# display_adapter.net
KiCad netlist of a schematic drawn in EAGLE
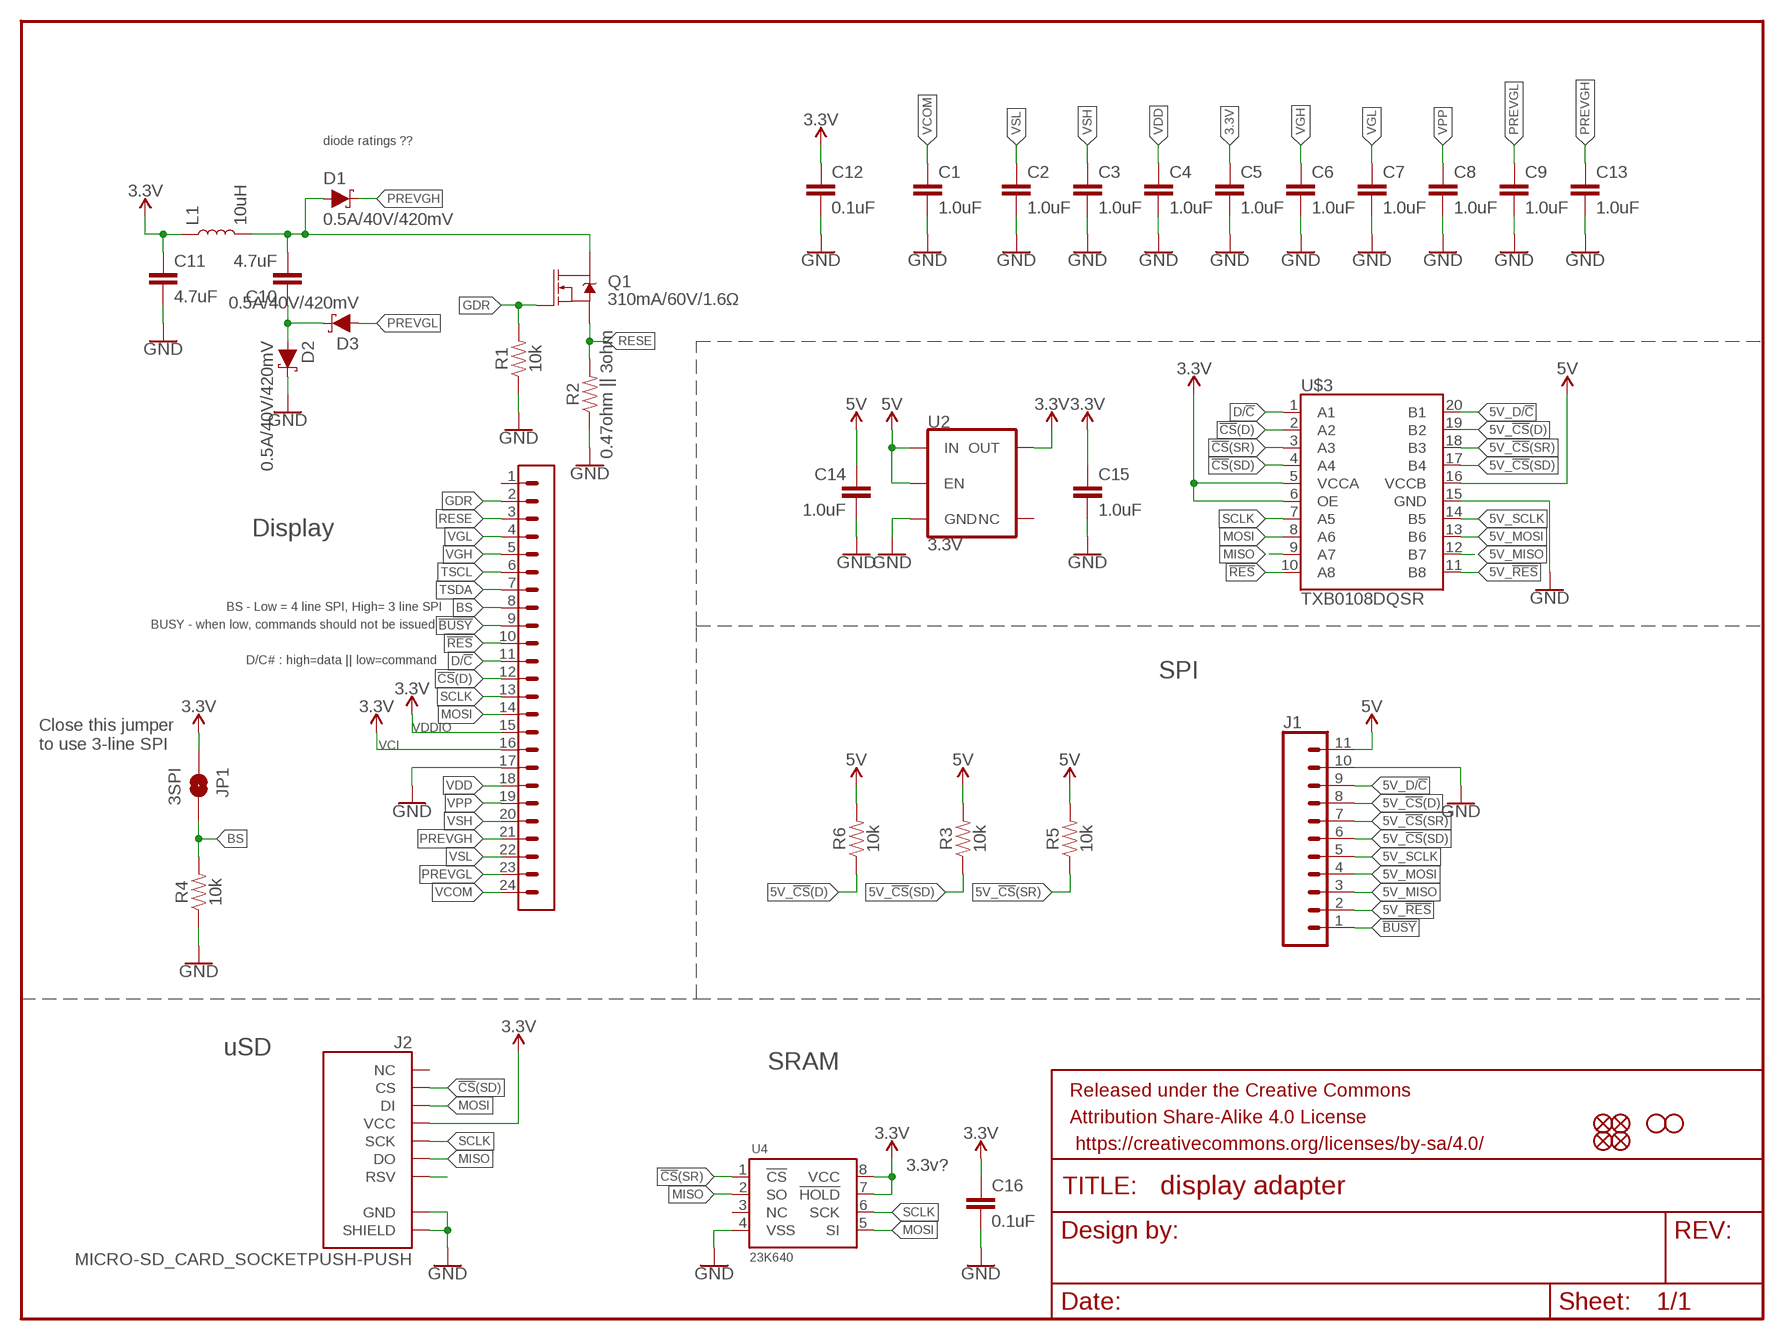
[diagram p0: schematic, sheet 1]

(export (version "E")
  (design (tool "Eeschema 10.0.6"))
  (components
    (comp (ref "C1")
      (value "1.0uF")
      (footprint "eagle-import:0603")
      (libsource (lib "eagle-import") (part "1.0UF-0603-16V-10%"))
    )
    (comp (ref "C2")
      (value "1.0uF")
      (footprint "eagle-import:0805")
      (libsource (lib "eagle-import") (part "1.0UF-0805-25V-10%"))
    )
    (comp (ref "C3")
      (value "1.0uF")
      (footprint "eagle-import:0805")
      (libsource (lib "eagle-import") (part "1.0UF-0805-25V-10%"))
    )
    (comp (ref "C4")
      (value "1.0uF")
      (footprint "eagle-import:0805")
      (libsource (lib "eagle-import") (part "1.0UF-0805-25V-10%"))
    )
    (comp (ref "C5")
      (value "1.0uF")
      (footprint "eagle-import:0805")
      (libsource (lib "eagle-import") (part "1.0UF-0805-25V-10%"))
    )
    (comp (ref "C6")
      (value "1.0uF")
      (footprint "eagle-import:0805")
      (libsource (lib "eagle-import") (part "1.0UF-0805-25V-10%"))
    )
    (comp (ref "C7")
      (value "1.0uF")
      (footprint "eagle-import:0805")
      (libsource (lib "eagle-import") (part "1.0UF-0805-25V-10%"))
    )
    (comp (ref "C8")
      (value "1.0uF")
      (footprint "eagle-import:0805")
      (libsource (lib "eagle-import") (part "1.0UF-0805-25V-10%"))
    )
    (comp (ref "C9")
      (value "1.0uF")
      (footprint "eagle-import:0805")
      (libsource (lib "eagle-import") (part "1.0UF-0805-25V-10%"))
    )
    (comp (ref "C10")
      (value "4.7uF")
      (footprint "eagle-import:0805")
      (libsource (lib "eagle-import") (part "22UF-0805-6.3V-20%"))
    )
    (comp (ref "C11")
      (value "4.7uF")
      (footprint "eagle-import:0805")
      (libsource (lib "eagle-import") (part "22UF-0805-6.3V-20%"))
    )
    (comp (ref "C12")
      (value "0.1uF")
      (footprint "eagle-import:0603")
      (libsource (lib "eagle-import") (part "0.1UF-0603-25V-(+80/-20%)"))
    )
    (comp (ref "C13")
      (value "1.0uF")
      (footprint "eagle-import:0805")
      (libsource (lib "eagle-import") (part "1.0UF-0805-25V-10%"))
    )
    (comp (ref "C14")
      (value "1.0uF")
      (footprint "eagle-import:0603")
      (libsource (lib "eagle-import") (part "1.0UF-0603-16V-10%"))
    )
    (comp (ref "C15")
      (value "1.0uF")
      (footprint "eagle-import:0603")
      (libsource (lib "eagle-import") (part "1.0UF-0603-16V-10%"))
    )
    (comp (ref "C16")
      (value "0.1uF")
      (footprint "eagle-import:0603")
      (libsource (lib "eagle-import") (part "0.1UF-0603-25V-(+80/-20%)"))
    )
    (comp (ref "D1")
      (value "0.5A/40V/420mV")
      (footprint "eagle-import:SOD-323")
      (libsource (lib "eagle-import") (part "DIODE-SCHOTTKY-PMEG4005EJ"))
    )
    (comp (ref "D2")
      (value "0.5A/40V/420mV")
      (footprint "eagle-import:SOD-323")
      (libsource (lib "eagle-import") (part "DIODE-SCHOTTKY-PMEG4005EJ"))
    )
    (comp (ref "D3")
      (value "0.5A/40V/420mV")
      (footprint "eagle-import:SOD-323")
      (libsource (lib "eagle-import") (part "DIODE-SCHOTTKY-PMEG4005EJ"))
    )
    (comp (ref "FD1")
      (value "FIDUCIALUFIDUCIAL")
      (footprint "eagle-import:FIDUCIAL-MICRO")
      (libsource (lib "eagle-import") (part "FIDUCIALUFIDUCIAL"))
    )
    (comp (ref "FD2")
      (value "FIDUCIALUFIDUCIAL")
      (footprint "eagle-import:FIDUCIAL-MICRO")
      (libsource (lib "eagle-import") (part "FIDUCIALUFIDUCIAL"))
    )
    (comp (ref "FD3")
      (value "FIDUCIALUFIDUCIAL")
      (footprint "eagle-import:FIDUCIAL-MICRO")
      (libsource (lib "eagle-import") (part "FIDUCIALUFIDUCIAL"))
    )
    (comp (ref "FD4")
      (value "FIDUCIALUFIDUCIAL")
      (footprint "eagle-import:FIDUCIAL-MICRO")
      (libsource (lib "eagle-import") (part "FIDUCIALUFIDUCIAL"))
    )
    (comp (ref "FRAME1")
      (value "FRAME-LETTER")
      (footprint "eagle-import:CREATIVE_COMMONS")
      (libsource (lib "eagle-import") (part "FRAME-LETTER"))
    )
    (comp (ref "H1")
      (value "STAND-OFF")
      (footprint "eagle-import:STAND-OFF")
      (libsource (lib "eagle-import") (part "STAND-OFF"))
    )
    (comp (ref "H2")
      (value "STAND-OFF")
      (footprint "eagle-import:STAND-OFF")
      (libsource (lib "eagle-import") (part "STAND-OFF"))
    )
    (comp (ref "J1")
      (value "CONN_111X11_NO_SILK")
      (footprint "eagle-import:1X11_NO_SILK")
      (libsource (lib "eagle-import") (part "CONN_111X11_NO_SILK"))
    )
    (comp (ref "J2")
      (value "MICRO-SD_CARD_SOCKETPUSH-PUSH")
      (footprint "eagle-import:MICRO-SD-SOCKET")
      (libsource (lib "eagle-import") (part "MICRO-SD_CARD_SOCKETPUSH-PUSH"))
    )
    (comp (ref "JP1")
      (value "3SPI")
      (footprint "eagle-import:SMT-JUMPER_2_NO_SILK")
      (libsource (lib "eagle-import") (part "JUMPER-SMT_2_NO_SILK"))
    )
    (comp (ref "L1")
      (value "10uH")
      (footprint "eagle-import:INDUCTOR_4.7UH")
      (libsource (lib "eagle-import") (part "INDUCTOR-CDRH-10UH"))
    )
    (comp (ref "Q1")
      (value "310mA/60V/1.6Ω")
      (footprint "eagle-import:SOT323")
      (libsource (lib "eagle-import") (part "MOSFET-NCH-2N7002PW"))
    )
    (comp (ref "R1")
      (value "10k")
      (footprint "eagle-import:0603")
      (libsource (lib "eagle-import") (part "10KOHM-0603-1/10W-1%"))
    )
    (comp (ref "R2")
      (value "0.47ohm || 3ohm")
      (footprint "eagle-import:0603")
      (libsource (lib "eagle-import") (part "RESISTOR0603"))
    )
    (comp (ref "R3")
      (value "10k")
      (footprint "eagle-import:0603")
      (libsource (lib "eagle-import") (part "10KOHM-0603-1/10W-1%"))
    )
    (comp (ref "R4")
      (value "10k")
      (footprint "eagle-import:0603")
      (libsource (lib "eagle-import") (part "10KOHM-0603-1/10W-1%"))
    )
    (comp (ref "R5")
      (value "10k")
      (footprint "eagle-import:0603")
      (libsource (lib "eagle-import") (part "10KOHM-0603-1/10W-1%"))
    )
    (comp (ref "R6")
      (value "10k")
      (footprint "eagle-import:0603")
      (libsource (lib "eagle-import") (part "10KOHM-0603-1/10W-1%"))
    )
    (comp (ref "U$1")
      (value "24_PIN_FPC_0.5MM")
      (footprint "eagle-import:24_PIN_FPC_0.5MM")
      (libsource (lib "eagle-import") (part "24_PIN_FPC_0.5MM"))
    )
    (comp (ref "U$3")
      (value "TXB0108DQSR")
      (footprint "eagle-import:UFDFN-20")
      (libsource (lib "eagle-import") (part "TXB0108"))
    )
    (comp (ref "U2")
      (value "3.3V")
      (footprint "eagle-import:SOT23-5")
      (libsource (lib "eagle-import") (part "V_REG_AP2112K-3.3V"))
    )
    (comp (ref "U4")
      (value "23K640")
      (footprint "eagle-import:SO08")
      (libsource (lib "eagle-import") (part "23K640"))
    )
  )
  (nets
    (net (code "1") (name "/5V_D{slash}~{C}") (class "Default")
      (node (ref "J1") (pin "9") (pinfunction "9_9") (pintype "passive"))
      (node (ref "U$3") (pin "20") (pinfunction "B1_20") (pintype "bidirectional"))
    )
    (net (code "2") (name "/5V_~{CS}(D)") (class "Default")
      (node (ref "J1") (pin "8") (pinfunction "8_8") (pintype "passive"))
      (node (ref "R6") (pin "1") (pinfunction "1_1") (pintype "passive"))
      (node (ref "U$3") (pin "19") (pinfunction "B2_19") (pintype "bidirectional"))
    )
    (net (code "3") (name "/5V_~{CS}(SD)") (class "Default")
      (node (ref "J1") (pin "6") (pinfunction "6_6") (pintype "passive"))
      (node (ref "R3") (pin "1") (pinfunction "1_1") (pintype "passive"))
      (node (ref "U$3") (pin "17") (pinfunction "B4_17") (pintype "bidirectional"))
    )
    (net (code "4") (name "/5V_~{CS}(SR)") (class "Default")
      (node (ref "J1") (pin "7") (pinfunction "7_7") (pintype "passive"))
      (node (ref "R5") (pin "1") (pinfunction "1_1") (pintype "passive"))
      (node (ref "U$3") (pin "18") (pinfunction "B3_18") (pintype "bidirectional"))
    )
    (net (code "5") (name "/5V_~{RES}") (class "Default")
      (node (ref "J1") (pin "2") (pinfunction "2_2") (pintype "passive"))
      (node (ref "U$3") (pin "11") (pinfunction "B8_11") (pintype "bidirectional"))
    )
    (net (code "6") (name "/D{slash}~{C}") (class "Default")
      (node (ref "U$1") (pin "11") (pinfunction "11_11") (pintype "bidirectional"))
      (node (ref "U$3") (pin "1") (pinfunction "A1_1") (pintype "bidirectional"))
    )
    (net (code "7") (name "/~{BUSY}") (class "Default")
      (node (ref "J1") (pin "1") (pinfunction "1_1") (pintype "passive"))
      (node (ref "U$1") (pin "9") (pinfunction "9_9") (pintype "bidirectional"))
    )
    (net (code "8") (name "/~{CS}(D)") (class "Default")
      (node (ref "U$1") (pin "12") (pinfunction "12_12") (pintype "bidirectional"))
      (node (ref "U$3") (pin "2") (pinfunction "A2_2") (pintype "bidirectional"))
    )
    (net (code "9") (name "/~{CS}(SD)") (class "Default")
      (node (ref "J2") (pin "CS") (pinfunction "CS_CS") (pintype "bidirectional"))
      (node (ref "U$3") (pin "4") (pinfunction "A4_4") (pintype "bidirectional"))
    )
    (net (code "10") (name "/~{CS}(SR)") (class "Default")
      (node (ref "U$3") (pin "3") (pinfunction "A3_3") (pintype "bidirectional"))
      (node (ref "U4") (pin "1") (pinfunction "~{CS}_1") (pintype "bidirectional"))
    )
    (net (code "11") (name "/~{RES}") (class "Default")
      (node (ref "U$1") (pin "10") (pinfunction "10_10") (pintype "bidirectional"))
      (node (ref "U$3") (pin "10") (pinfunction "A8_10") (pintype "bidirectional"))
    )
    (net (code "12") (name "3.3V") (class "Default")
      (node (ref "C11") (pin "1") (pinfunction "1_1") (pintype "passive"))
      (node (ref "C12") (pin "1") (pinfunction "1_1") (pintype "passive"))
      (node (ref "C15") (pin "1") (pinfunction "1_1") (pintype "passive"))
      (node (ref "C16") (pin "1") (pinfunction "1_1") (pintype "passive"))
      (node (ref "C5") (pin "1") (pinfunction "1_1") (pintype "passive"))
      (node (ref "J2") (pin "VCC") (pinfunction "VCC_VCC") (pintype "bidirectional"))
      (node (ref "JP1") (pin "1") (pinfunction "1_1") (pintype "passive"))
      (node (ref "L1") (pin "P$1") (pinfunction "1_P$1") (pintype "passive"))
      (node (ref "U$1") (pin "15") (pinfunction "15_15") (pintype "bidirectional"))
      (node (ref "U$1") (pin "16") (pinfunction "16_16") (pintype "bidirectional"))
      (node (ref "U$3") (pin "5") (pinfunction "VCCA_5") (pintype "bidirectional"))
      (node (ref "U$3") (pin "6") (pinfunction "OE_6") (pintype "bidirectional"))
      (node (ref "U2") (pin "5") (pinfunction "OUT_5") (pintype "passive"))
      (node (ref "U4") (pin "7") (pinfunction "~{HOLD}_7") (pintype "bidirectional"))
      (node (ref "U4") (pin "8") (pinfunction "VCC_8") (pintype "bidirectional"))
    )
    (net (code "13") (name "5V") (class "Default")
      (node (ref "C14") (pin "1") (pinfunction "1_1") (pintype "passive"))
      (node (ref "J1") (pin "11") (pinfunction "11_11") (pintype "passive"))
      (node (ref "R3") (pin "2") (pinfunction "2_2") (pintype "passive"))
      (node (ref "R5") (pin "2") (pinfunction "2_2") (pintype "passive"))
      (node (ref "R6") (pin "2") (pinfunction "2_2") (pintype "passive"))
      (node (ref "U$3") (pin "16") (pinfunction "VCCB_16") (pintype "bidirectional"))
      (node (ref "U2") (pin "1") (pinfunction "IN_1") (pintype "input"))
      (node (ref "U2") (pin "3") (pinfunction "EN_3") (pintype "input"))
    )
    (net (code "14") (name "5V_MISO") (class "Default")
      (node (ref "J1") (pin "3") (pinfunction "3_3") (pintype "passive"))
      (node (ref "U$3") (pin "12") (pinfunction "B7_12") (pintype "bidirectional"))
    )
    (net (code "15") (name "5V_MOSI") (class "Default")
      (node (ref "J1") (pin "4") (pinfunction "4_4") (pintype "passive"))
      (node (ref "U$3") (pin "13") (pinfunction "B6_13") (pintype "bidirectional"))
    )
    (net (code "16") (name "5V_SCLK") (class "Default")
      (node (ref "J1") (pin "5") (pinfunction "5_5") (pintype "passive"))
      (node (ref "U$3") (pin "14") (pinfunction "B5_14") (pintype "bidirectional"))
    )
    (net (code "17") (name "BS") (class "Default")
      (node (ref "JP1") (pin "2") (pinfunction "2_2") (pintype "passive"))
      (node (ref "R4") (pin "2") (pinfunction "2_2") (pintype "passive"))
      (node (ref "U$1") (pin "8") (pinfunction "8_8") (pintype "bidirectional"))
    )
    (net (code "18") (name "GDR") (class "Default")
      (node (ref "Q1") (pin "1") (pinfunction "G_1") (pintype "bidirectional"))
      (node (ref "R1") (pin "2") (pinfunction "2_2") (pintype "passive"))
      (node (ref "U$1") (pin "2") (pinfunction "2_2") (pintype "bidirectional"))
    )
    (net (code "19") (name "GND") (class "Default")
      (node (ref "C1") (pin "2") (pinfunction "2_2") (pintype "passive"))
      (node (ref "C11") (pin "2") (pinfunction "2_2") (pintype "passive"))
      (node (ref "C12") (pin "2") (pinfunction "2_2") (pintype "passive"))
      (node (ref "C13") (pin "2") (pinfunction "2_2") (pintype "passive"))
      (node (ref "C14") (pin "2") (pinfunction "2_2") (pintype "passive"))
      (node (ref "C15") (pin "2") (pinfunction "2_2") (pintype "passive"))
      (node (ref "C16") (pin "2") (pinfunction "2_2") (pintype "passive"))
      (node (ref "C2") (pin "2") (pinfunction "2_2") (pintype "passive"))
      (node (ref "C3") (pin "2") (pinfunction "2_2") (pintype "passive"))
      (node (ref "C4") (pin "2") (pinfunction "2_2") (pintype "passive"))
      (node (ref "C5") (pin "2") (pinfunction "2_2") (pintype "passive"))
      (node (ref "C6") (pin "2") (pinfunction "2_2") (pintype "passive"))
      (node (ref "C7") (pin "2") (pinfunction "2_2") (pintype "passive"))
      (node (ref "C8") (pin "2") (pinfunction "2_2") (pintype "passive"))
      (node (ref "C9") (pin "2") (pinfunction "2_2") (pintype "passive"))
      (node (ref "D2") (pin "C") (pinfunction "C_C") (pintype "passive"))
      (node (ref "J1") (pin "10") (pinfunction "10_10") (pintype "passive"))
      (node (ref "J2") (pin "CD1") (pinfunction "SHIELD_CD1") (pintype "bidirectional"))
      (node (ref "J2") (pin "GND") (pinfunction "GND_GND") (pintype "bidirectional"))
      (node (ref "R1") (pin "1") (pinfunction "1_1") (pintype "passive"))
      (node (ref "R2") (pin "1") (pinfunction "1_1") (pintype "passive"))
      (node (ref "R4") (pin "1") (pinfunction "1_1") (pintype "passive"))
      (node (ref "U$1") (pin "17") (pinfunction "17_17") (pintype "bidirectional"))
      (node (ref "U$3") (pin "15") (pinfunction "GND_15") (pintype "bidirectional"))
      (node (ref "U2") (pin "2") (pinfunction "GND_2") (pintype "input"))
      (node (ref "U4") (pin "4") (pinfunction "VSS_4") (pintype "bidirectional"))
    )
    (net (code "20") (name "MISO") (class "Default")
      (node (ref "J2") (pin "DO") (pinfunction "DO_DO") (pintype "bidirectional"))
      (node (ref "U$3") (pin "9") (pinfunction "A7_9") (pintype "bidirectional"))
      (node (ref "U4") (pin "2") (pinfunction "SO_2") (pintype "bidirectional"))
    )
    (net (code "21") (name "MOSI") (class "Default")
      (node (ref "J2") (pin "DI") (pinfunction "DI_DI") (pintype "bidirectional"))
      (node (ref "U$1") (pin "14") (pinfunction "14_14") (pintype "bidirectional"))
      (node (ref "U$3") (pin "8") (pinfunction "A6_8") (pintype "bidirectional"))
      (node (ref "U4") (pin "5") (pinfunction "SI_5") (pintype "bidirectional"))
    )
    (net (code "22") (name "Net-(C10-Pad1)") (class "Default")
      (node (ref "C10") (pin "1") (pinfunction "1_1") (pintype "passive"))
      (node (ref "D2") (pin "A") (pinfunction "A_A") (pintype "passive"))
      (node (ref "D3") (pin "C") (pinfunction "C_C") (pintype "passive"))
    )
    (net (code "23") (name "Net-(L1-2)") (class "Default")
      (node (ref "C10") (pin "2") (pinfunction "2_2") (pintype "passive"))
      (node (ref "D1") (pin "A") (pinfunction "A_A") (pintype "passive"))
      (node (ref "L1") (pin "P$2") (pinfunction "2_P$2") (pintype "passive"))
      (node (ref "Q1") (pin "3") (pinfunction "D_3") (pintype "bidirectional"))
    )
    (net (code "24") (name "PREVGH") (class "Default")
      (node (ref "C13") (pin "1") (pinfunction "1_1") (pintype "passive"))
      (node (ref "D1") (pin "C") (pinfunction "C_C") (pintype "passive"))
      (node (ref "U$1") (pin "21") (pinfunction "21_21") (pintype "bidirectional"))
    )
    (net (code "25") (name "PREVGL") (class "Default")
      (node (ref "C9") (pin "1") (pinfunction "1_1") (pintype "passive"))
      (node (ref "D3") (pin "A") (pinfunction "A_A") (pintype "passive"))
      (node (ref "U$1") (pin "23") (pinfunction "23_23") (pintype "bidirectional"))
    )
    (net (code "26") (name "RESE") (class "Default")
      (node (ref "Q1") (pin "2") (pinfunction "S_2") (pintype "bidirectional"))
      (node (ref "R2") (pin "2") (pinfunction "2_2") (pintype "passive"))
      (node (ref "U$1") (pin "3") (pinfunction "3_3") (pintype "bidirectional"))
    )
    (net (code "27") (name "SCLK") (class "Default")
      (node (ref "J2") (pin "SCLK") (pinfunction "SCK_SCLK") (pintype "bidirectional"))
      (node (ref "U$1") (pin "13") (pinfunction "13_13") (pintype "bidirectional"))
      (node (ref "U$3") (pin "7") (pinfunction "A5_7") (pintype "bidirectional"))
      (node (ref "U4") (pin "6") (pinfunction "SCK_6") (pintype "bidirectional"))
    )
    (net (code "28") (name "TSCL") (class "Default")
      (node (ref "U$1") (pin "6") (pinfunction "6_6") (pintype "bidirectional"))
    )
    (net (code "29") (name "TSDA") (class "Default")
      (node (ref "U$1") (pin "7") (pinfunction "7_7") (pintype "bidirectional"))
    )
    (net (code "30") (name "VCOM") (class "Default")
      (node (ref "C1") (pin "1") (pinfunction "1_1") (pintype "passive"))
      (node (ref "U$1") (pin "24") (pinfunction "24_24") (pintype "bidirectional"))
    )
    (net (code "31") (name "VDD") (class "Default")
      (node (ref "C4") (pin "1") (pinfunction "1_1") (pintype "passive"))
      (node (ref "U$1") (pin "18") (pinfunction "18_18") (pintype "bidirectional"))
    )
    (net (code "32") (name "VGH") (class "Default")
      (node (ref "C6") (pin "1") (pinfunction "1_1") (pintype "passive"))
      (node (ref "U$1") (pin "5") (pinfunction "5_5") (pintype "bidirectional"))
    )
    (net (code "33") (name "VGL") (class "Default")
      (node (ref "C7") (pin "1") (pinfunction "1_1") (pintype "passive"))
      (node (ref "U$1") (pin "4") (pinfunction "4_4") (pintype "bidirectional"))
    )
    (net (code "34") (name "VPP") (class "Default")
      (node (ref "C8") (pin "1") (pinfunction "1_1") (pintype "passive"))
      (node (ref "U$1") (pin "19") (pinfunction "19_19") (pintype "bidirectional"))
    )
    (net (code "35") (name "VSH") (class "Default")
      (node (ref "C3") (pin "1") (pinfunction "1_1") (pintype "passive"))
      (node (ref "U$1") (pin "20") (pinfunction "20_20") (pintype "bidirectional"))
    )
    (net (code "36") (name "VSL") (class "Default")
      (node (ref "C2") (pin "1") (pinfunction "1_1") (pintype "passive"))
      (node (ref "U$1") (pin "22") (pinfunction "22_22") (pintype "bidirectional"))
    )
    (net (code "37") (name "unconnected-(J2-NC-PadRSV2)") (class "Default")
      (node (ref "J2") (pin "RSV2") (pinfunction "NC_RSV2") (pintype "bidirectional"))
    )
    (net (code "38") (name "unconnected-(J2-RSV-PadRSV1)") (class "Default")
      (node (ref "J2") (pin "RSV1") (pinfunction "RSV_RSV1") (pintype "bidirectional"))
    )
    (net (code "39") (name "unconnected-(U$1-Pad1)") (class "Default")
      (node (ref "U$1") (pin "1") (pinfunction "1_1") (pintype "bidirectional"))
    )
    (net (code "40") (name "unconnected-(U2-NC-Pad4)") (class "Default")
      (node (ref "U2") (pin "4") (pinfunction "NC_4") (pintype "no_connect"))
    )
    (net (code "41") (name "unconnected-(U4-NC-Pad3)") (class "Default")
      (node (ref "U4") (pin "3") (pinfunction "NC_3") (pintype "bidirectional"))
    )
  )
)
